# Voltage_Sense.net
KiCad netlist of a schematic drawn in Altium Designer
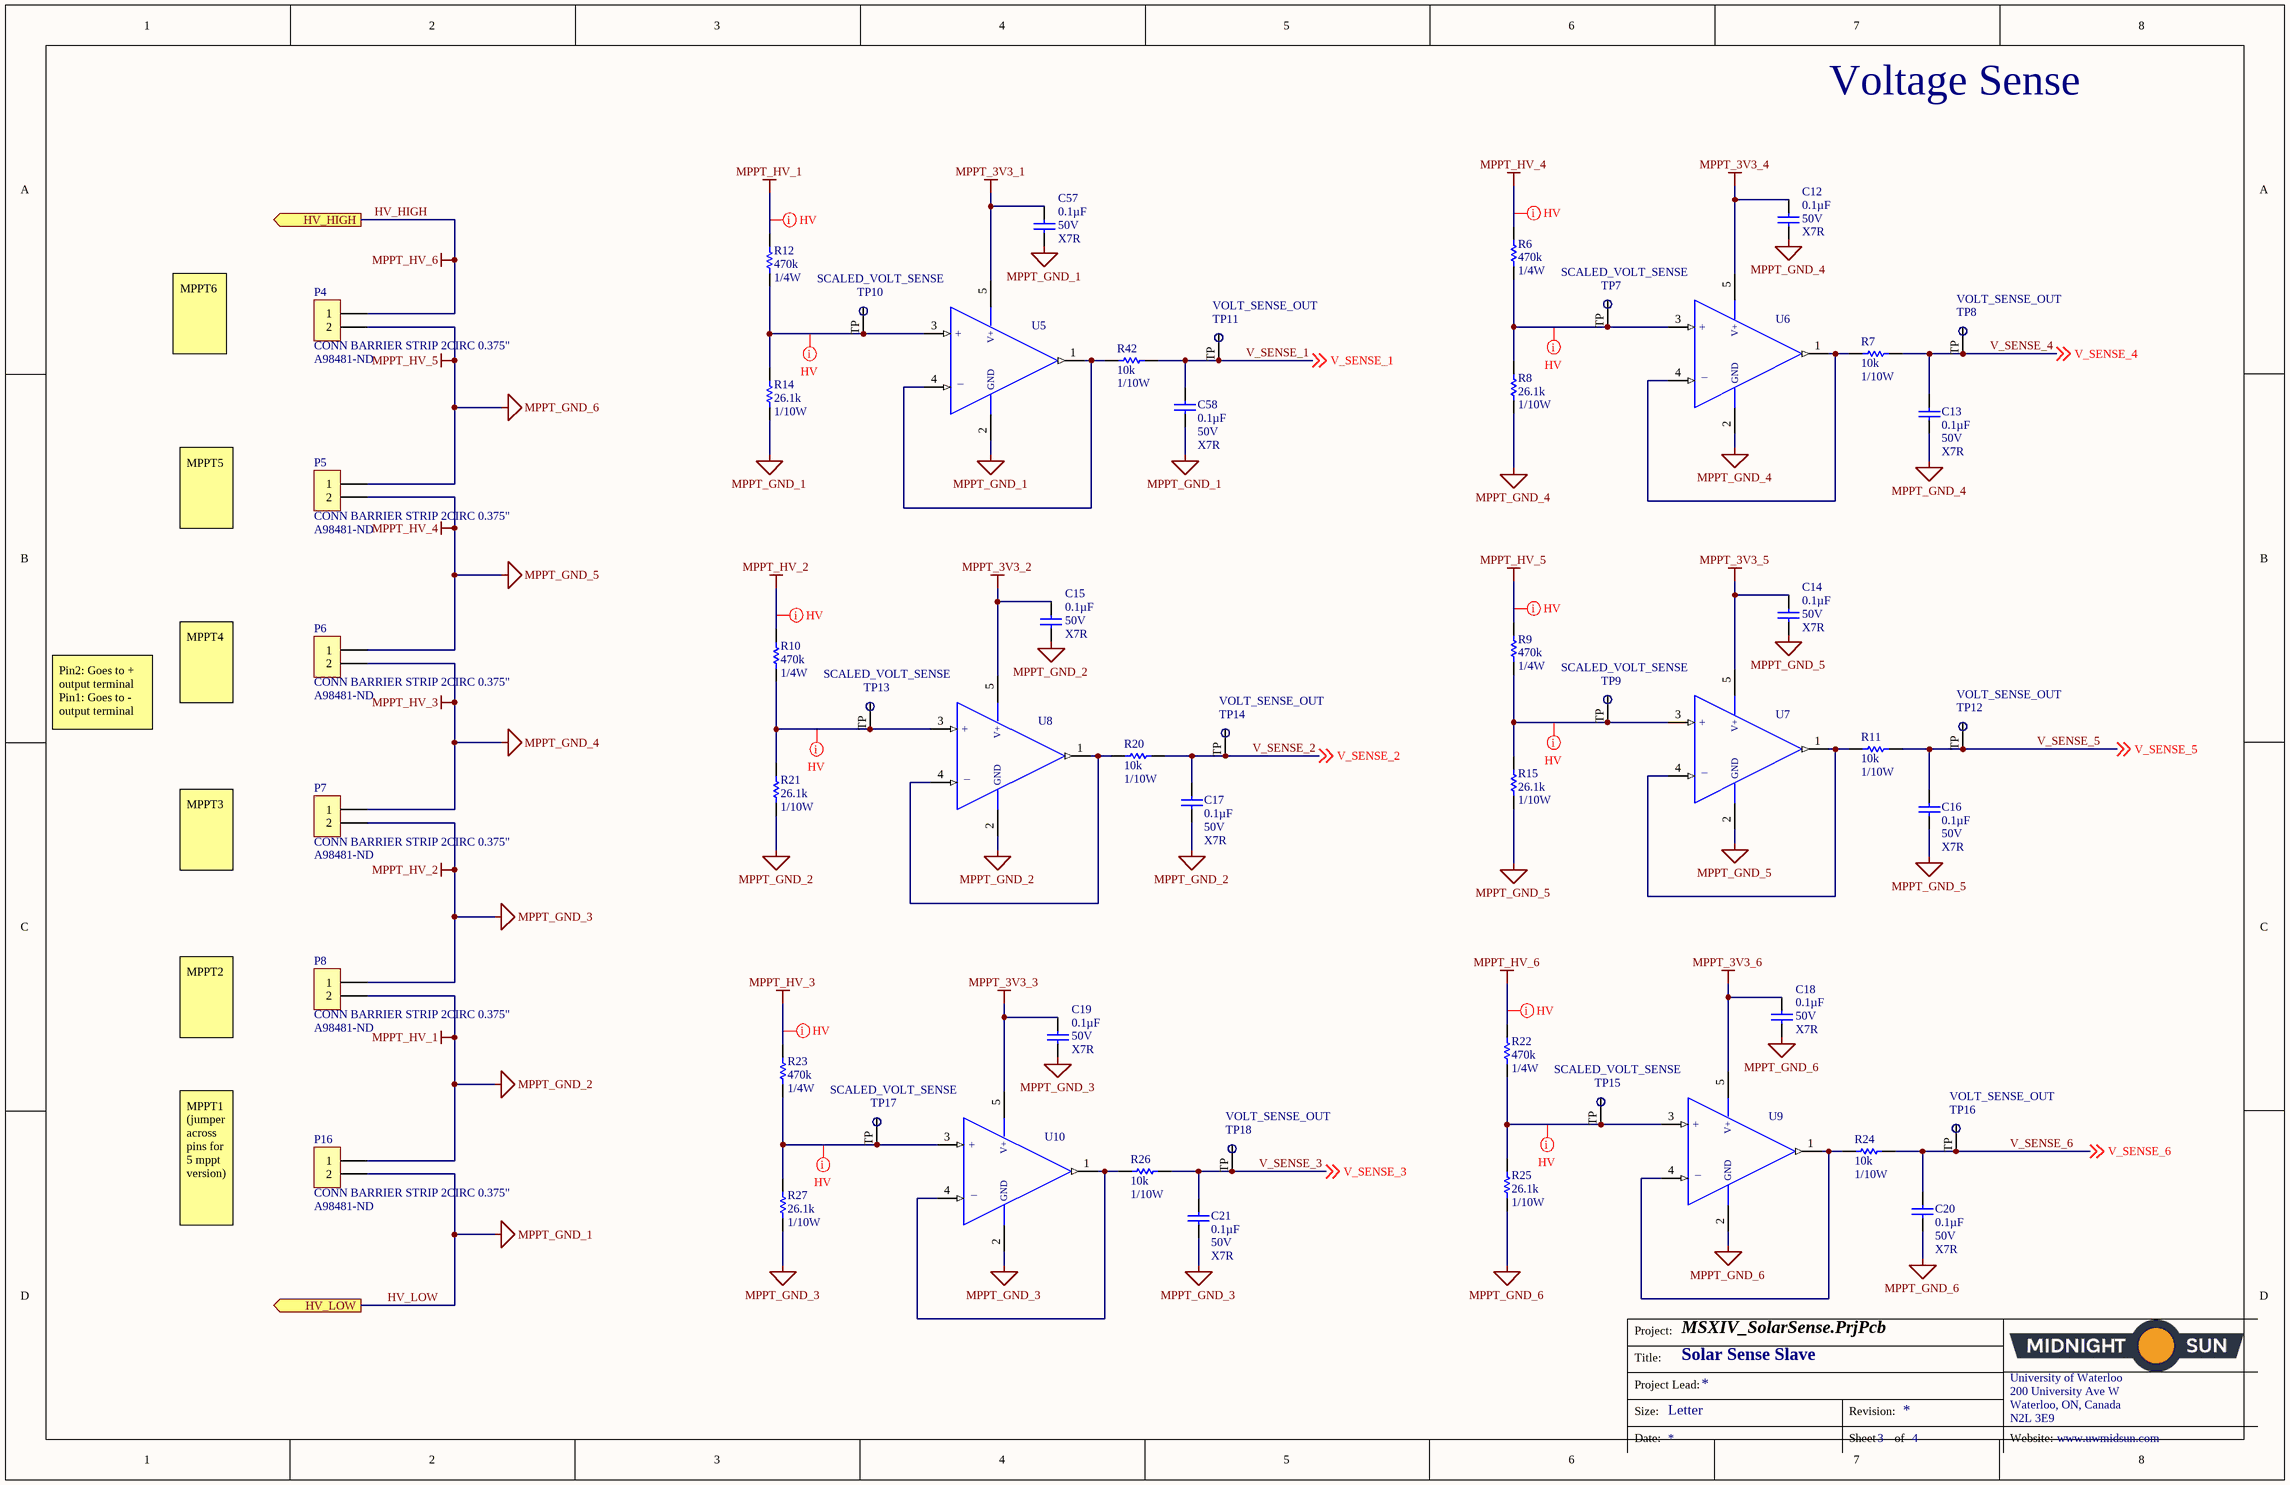
[diagram p0: Voltage_Sense.SchDoc]

(export (version "E")
  (design (tool "Eeschema 10.0.6"))
  (components
    (comp (ref "C12")
      (value "CAP CER 0.1UF 50V 10% X7R 0603")
      (footprint "CAP, 0603")
      (description "0.10µF ±10% 50V Ceramic Capacitor X7R 0603 (1608 Metric)")
      (fields
        (field (name "TOLERANCE") "±10%")
        (field (name "CAPACITANCE") "0.1µF")
        (field (name "VOLTAGE") "50V")
        (field (name "TEMPERATURE COEFFICIENT") "X7R")
      )
      (libsource (lib "Schematic Diagrams") (part "CAP CER 0.1UF 50V 10% X7R 0603"))
    )
    (comp (ref "C13")
      (value "CAP CER 0.1UF 50V 10% X7R 0603")
      (footprint "CAP, 0603")
      (description "0.10µF ±10% 50V Ceramic Capacitor X7R 0603 (1608 Metric)")
      (fields
        (field (name "TOLERANCE") "±10%")
        (field (name "CAPACITANCE") "0.1µF")
        (field (name "VOLTAGE") "50V")
        (field (name "TEMPERATURE COEFFICIENT") "X7R")
      )
      (libsource (lib "Schematic Diagrams") (part "CAP CER 0.1UF 50V 10% X7R 0603"))
    )
    (comp (ref "C14")
      (value "CAP CER 0.1UF 50V 10% X7R 0603")
      (footprint "CAP, 0603")
      (description "0.10µF ±10% 50V Ceramic Capacitor X7R 0603 (1608 Metric)")
      (fields
        (field (name "TOLERANCE") "±10%")
        (field (name "CAPACITANCE") "0.1µF")
        (field (name "VOLTAGE") "50V")
        (field (name "TEMPERATURE COEFFICIENT") "X7R")
      )
      (libsource (lib "Schematic Diagrams") (part "CAP CER 0.1UF 50V 10% X7R 0603"))
    )
    (comp (ref "C15")
      (value "CAP CER 0.1UF 50V 10% X7R 0603")
      (footprint "CAP, 0603")
      (description "0.10µF ±10% 50V Ceramic Capacitor X7R 0603 (1608 Metric)")
      (fields
        (field (name "TOLERANCE") "±10%")
        (field (name "CAPACITANCE") "0.1µF")
        (field (name "VOLTAGE") "50V")
        (field (name "TEMPERATURE COEFFICIENT") "X7R")
      )
      (libsource (lib "Schematic Diagrams") (part "CAP CER 0.1UF 50V 10% X7R 0603"))
    )
    (comp (ref "C16")
      (value "CAP CER 0.1UF 50V 10% X7R 0603")
      (footprint "CAP, 0603")
      (description "0.10µF ±10% 50V Ceramic Capacitor X7R 0603 (1608 Metric)")
      (fields
        (field (name "TOLERANCE") "±10%")
        (field (name "CAPACITANCE") "0.1µF")
        (field (name "VOLTAGE") "50V")
        (field (name "TEMPERATURE COEFFICIENT") "X7R")
      )
      (libsource (lib "Schematic Diagrams") (part "CAP CER 0.1UF 50V 10% X7R 0603"))
    )
    (comp (ref "C17")
      (value "CAP CER 0.1UF 50V 10% X7R 0603")
      (footprint "CAP, 0603")
      (description "0.10µF ±10% 50V Ceramic Capacitor X7R 0603 (1608 Metric)")
      (fields
        (field (name "TOLERANCE") "±10%")
        (field (name "CAPACITANCE") "0.1µF")
        (field (name "VOLTAGE") "50V")
        (field (name "TEMPERATURE COEFFICIENT") "X7R")
      )
      (libsource (lib "Schematic Diagrams") (part "CAP CER 0.1UF 50V 10% X7R 0603"))
    )
    (comp (ref "C18")
      (value "CAP CER 0.1UF 50V 10% X7R 0603")
      (footprint "CAP, 0603")
      (description "0.10µF ±10% 50V Ceramic Capacitor X7R 0603 (1608 Metric)")
      (fields
        (field (name "TOLERANCE") "±10%")
        (field (name "CAPACITANCE") "0.1µF")
        (field (name "VOLTAGE") "50V")
        (field (name "TEMPERATURE COEFFICIENT") "X7R")
      )
      (libsource (lib "Schematic Diagrams") (part "CAP CER 0.1UF 50V 10% X7R 0603"))
    )
    (comp (ref "C19")
      (value "CAP CER 0.1UF 50V 10% X7R 0603")
      (footprint "CAP, 0603")
      (description "0.10µF ±10% 50V Ceramic Capacitor X7R 0603 (1608 Metric)")
      (fields
        (field (name "TOLERANCE") "±10%")
        (field (name "CAPACITANCE") "0.1µF")
        (field (name "VOLTAGE") "50V")
        (field (name "TEMPERATURE COEFFICIENT") "X7R")
      )
      (libsource (lib "Schematic Diagrams") (part "CAP CER 0.1UF 50V 10% X7R 0603"))
    )
    (comp (ref "C20")
      (value "CAP CER 0.1UF 50V 10% X7R 0603")
      (footprint "CAP, 0603")
      (description "0.10µF ±10% 50V Ceramic Capacitor X7R 0603 (1608 Metric)")
      (fields
        (field (name "TOLERANCE") "±10%")
        (field (name "CAPACITANCE") "0.1µF")
        (field (name "VOLTAGE") "50V")
        (field (name "TEMPERATURE COEFFICIENT") "X7R")
      )
      (libsource (lib "Schematic Diagrams") (part "CAP CER 0.1UF 50V 10% X7R 0603"))
    )
    (comp (ref "C21")
      (value "CAP CER 0.1UF 50V 10% X7R 0603")
      (footprint "CAP, 0603")
      (description "0.10µF ±10% 50V Ceramic Capacitor X7R 0603 (1608 Metric)")
      (fields
        (field (name "TOLERANCE") "±10%")
        (field (name "CAPACITANCE") "0.1µF")
        (field (name "VOLTAGE") "50V")
        (field (name "TEMPERATURE COEFFICIENT") "X7R")
      )
      (libsource (lib "Schematic Diagrams") (part "CAP CER 0.1UF 50V 10% X7R 0603"))
    )
    (comp (ref "C57")
      (value "CAP CER 0.1UF 50V 10% X7R 0603")
      (footprint "CAP, 0603")
      (description "0.10µF ±10% 50V Ceramic Capacitor X7R 0603 (1608 Metric)")
      (fields
        (field (name "TOLERANCE") "±10%")
        (field (name "CAPACITANCE") "0.1µF")
        (field (name "VOLTAGE") "50V")
        (field (name "TEMPERATURE COEFFICIENT") "X7R")
      )
      (libsource (lib "Schematic Diagrams") (part "CAP CER 0.1UF 50V 10% X7R 0603"))
    )
    (comp (ref "C58")
      (value "CAP CER 0.1UF 50V 10% X7R 0603")
      (footprint "CAP, 0603")
      (description "0.10µF ±10% 50V Ceramic Capacitor X7R 0603 (1608 Metric)")
      (fields
        (field (name "TOLERANCE") "±10%")
        (field (name "CAPACITANCE") "0.1µF")
        (field (name "VOLTAGE") "50V")
        (field (name "TEMPERATURE COEFFICIENT") "X7R")
      )
      (libsource (lib "Schematic Diagrams") (part "CAP CER 0.1UF 50V 10% X7R 0603"))
    )
    (comp (ref "P4")
      (value "CONN BARRIER STRIP 2CIRC 0.375\"")
      (footprint "TE_3-1437652-9")
      (description "Barrier Terminal Blocks 2P TRI-BARRIER .375")
      (fields
        (field (name "MANUFACTURER") "TE Connectivity")
        (field (name "MANUFACTURER PART NUMBER") "6PCV-02-006")
        (field (name "SUPPLIER PART NUMBER 1") "A98481-ND")
      )
      (libsource (lib "Schematic Diagrams") (part "CONN BARRIER STRIP 2CIRC 0.375{dblquote}"))
    )
    (comp (ref "P5")
      (value "CONN BARRIER STRIP 2CIRC 0.375\"")
      (footprint "TE_3-1437652-9")
      (description "Barrier Terminal Blocks 2P TRI-BARRIER .375")
      (fields
        (field (name "MANUFACTURER") "TE Connectivity")
        (field (name "MANUFACTURER PART NUMBER") "6PCV-02-006")
        (field (name "SUPPLIER PART NUMBER 1") "A98481-ND")
      )
      (libsource (lib "Schematic Diagrams") (part "CONN BARRIER STRIP 2CIRC 0.375{dblquote}"))
    )
    (comp (ref "P6")
      (value "CONN BARRIER STRIP 2CIRC 0.375\"")
      (footprint "TE_3-1437652-9")
      (description "Barrier Terminal Blocks 2P TRI-BARRIER .375")
      (fields
        (field (name "MANUFACTURER") "TE Connectivity")
        (field (name "MANUFACTURER PART NUMBER") "6PCV-02-006")
        (field (name "SUPPLIER PART NUMBER 1") "A98481-ND")
      )
      (libsource (lib "Schematic Diagrams") (part "CONN BARRIER STRIP 2CIRC 0.375{dblquote}"))
    )
    (comp (ref "P7")
      (value "CONN BARRIER STRIP 2CIRC 0.375\"")
      (footprint "TE_3-1437652-9")
      (description "Barrier Terminal Blocks 2P TRI-BARRIER .375")
      (fields
        (field (name "MANUFACTURER") "TE Connectivity")
        (field (name "MANUFACTURER PART NUMBER") "6PCV-02-006")
        (field (name "SUPPLIER PART NUMBER 1") "A98481-ND")
      )
      (libsource (lib "Schematic Diagrams") (part "CONN BARRIER STRIP 2CIRC 0.375{dblquote}"))
    )
    (comp (ref "P8")
      (value "CONN BARRIER STRIP 2CIRC 0.375\"")
      (footprint "TE_3-1437652-9")
      (description "Barrier Terminal Blocks 2P TRI-BARRIER .375")
      (fields
        (field (name "MANUFACTURER") "TE Connectivity")
        (field (name "MANUFACTURER PART NUMBER") "6PCV-02-006")
        (field (name "SUPPLIER PART NUMBER 1") "A98481-ND")
      )
      (libsource (lib "Schematic Diagrams") (part "CONN BARRIER STRIP 2CIRC 0.375{dblquote}"))
    )
    (comp (ref "P16")
      (value "CONN BARRIER STRIP 2CIRC 0.375\"")
      (footprint "TE_3-1437652-9")
      (description "Barrier Terminal Blocks 2P TRI-BARRIER .375")
      (fields
        (field (name "MANUFACTURER") "TE Connectivity")
        (field (name "MANUFACTURER PART NUMBER") "6PCV-02-006")
        (field (name "SUPPLIER PART NUMBER 1") "A98481-ND")
      )
      (libsource (lib "Schematic Diagrams") (part "CONN BARRIER STRIP 2CIRC 0.375{dblquote}"))
    )
    (comp (ref "R6")
      (value "RES 470K OHM 1% 1/4W 0603")
      (footprint "RES, 0603")
      (description "RES SMD 470K OHM 1% 1/4W 0603")
      (fields
        (field (name "TOLERANCE") "±1%")
        (field (name "RESISTANCE") "470k")
        (field (name "POWER") "1/4W")
      )
      (libsource (lib "Schematic Diagrams") (part "RES 470K OHM 1% 1/4W 0603"))
    )
    (comp (ref "R7")
      (value "RES 10K OHM 1% 1/10W 0603")
      (footprint "RES, 0603")
      (description "RES SMD 10K OHM 1% 1/10W 0603")
      (fields
        (field (name "TOLERANCE") "±1%")
        (field (name "RESISTANCE") "10k")
        (field (name "POWER") "1/10W")
      )
      (libsource (lib "Schematic Diagrams") (part "RES 10K OHM 1% 1/10W 0603"))
    )
    (comp (ref "R8")
      (value "RES 26.1K OHM 1% 1/10W 0603")
      (footprint "RES, 0603")
      (description "RES SMD 26.1K OHM 1% 1/10W 0603")
      (fields
        (field (name "TOLERANCE") "±1%")
        (field (name "RESISTANCE") "26.1k")
        (field (name "POWER") "1/10W")
      )
      (libsource (lib "Schematic Diagrams") (part "RES 26.1K OHM 1% 1/10W 0603"))
    )
    (comp (ref "R9")
      (value "RES 470K OHM 1% 1/4W 0603")
      (footprint "RES, 0603")
      (description "RES SMD 470K OHM 1% 1/4W 0603")
      (fields
        (field (name "TOLERANCE") "±1%")
        (field (name "RESISTANCE") "470k")
        (field (name "POWER") "1/4W")
      )
      (libsource (lib "Schematic Diagrams") (part "RES 470K OHM 1% 1/4W 0603"))
    )
    (comp (ref "R10")
      (value "RES 470K OHM 1% 1/4W 0603")
      (footprint "RES, 0603")
      (description "RES SMD 470K OHM 1% 1/4W 0603")
      (fields
        (field (name "TOLERANCE") "±1%")
        (field (name "RESISTANCE") "470k")
        (field (name "POWER") "1/4W")
      )
      (libsource (lib "Schematic Diagrams") (part "RES 470K OHM 1% 1/4W 0603"))
    )
    (comp (ref "R11")
      (value "RES 10K OHM 1% 1/10W 0603")
      (footprint "RES, 0603")
      (description "RES SMD 10K OHM 1% 1/10W 0603")
      (fields
        (field (name "TOLERANCE") "±1%")
        (field (name "RESISTANCE") "10k")
        (field (name "POWER") "1/10W")
      )
      (libsource (lib "Schematic Diagrams") (part "RES 10K OHM 1% 1/10W 0603"))
    )
    (comp (ref "R12")
      (value "RES 470K OHM 1% 1/4W 0603")
      (footprint "RES, 0603")
      (description "RES SMD 470K OHM 1% 1/4W 0603")
      (fields
        (field (name "TOLERANCE") "±1%")
        (field (name "RESISTANCE") "470k")
        (field (name "POWER") "1/4W")
      )
      (libsource (lib "Schematic Diagrams") (part "RES 470K OHM 1% 1/4W 0603"))
    )
    (comp (ref "R14")
      (value "RES 26.1K OHM 1% 1/10W 0603")
      (footprint "RES, 0603")
      (description "RES SMD 26.1K OHM 1% 1/10W 0603")
      (fields
        (field (name "TOLERANCE") "±1%")
        (field (name "RESISTANCE") "26.1k")
        (field (name "POWER") "1/10W")
      )
      (libsource (lib "Schematic Diagrams") (part "RES 26.1K OHM 1% 1/10W 0603"))
    )
    (comp (ref "R15")
      (value "RES 26.1K OHM 1% 1/10W 0603")
      (footprint "RES, 0603")
      (description "RES SMD 26.1K OHM 1% 1/10W 0603")
      (fields
        (field (name "TOLERANCE") "±1%")
        (field (name "RESISTANCE") "26.1k")
        (field (name "POWER") "1/10W")
      )
      (libsource (lib "Schematic Diagrams") (part "RES 26.1K OHM 1% 1/10W 0603"))
    )
    (comp (ref "R20")
      (value "RES 10K OHM 1% 1/10W 0603")
      (footprint "RES, 0603")
      (description "RES SMD 10K OHM 1% 1/10W 0603")
      (fields
        (field (name "TOLERANCE") "±1%")
        (field (name "RESISTANCE") "10k")
        (field (name "POWER") "1/10W")
      )
      (libsource (lib "Schematic Diagrams") (part "RES 10K OHM 1% 1/10W 0603"))
    )
    (comp (ref "R21")
      (value "RES 26.1K OHM 1% 1/10W 0603")
      (footprint "RES, 0603")
      (description "RES SMD 26.1K OHM 1% 1/10W 0603")
      (fields
        (field (name "TOLERANCE") "±1%")
        (field (name "RESISTANCE") "26.1k")
        (field (name "POWER") "1/10W")
      )
      (libsource (lib "Schematic Diagrams") (part "RES 26.1K OHM 1% 1/10W 0603"))
    )
    (comp (ref "R22")
      (value "RES 470K OHM 1% 1/4W 0603")
      (footprint "RES, 0603")
      (description "RES SMD 470K OHM 1% 1/4W 0603")
      (fields
        (field (name "TOLERANCE") "±1%")
        (field (name "RESISTANCE") "470k")
        (field (name "POWER") "1/4W")
      )
      (libsource (lib "Schematic Diagrams") (part "RES 470K OHM 1% 1/4W 0603"))
    )
    (comp (ref "R23")
      (value "RES 470K OHM 1% 1/4W 0603")
      (footprint "RES, 0603")
      (description "RES SMD 470K OHM 1% 1/4W 0603")
      (fields
        (field (name "TOLERANCE") "±1%")
        (field (name "RESISTANCE") "470k")
        (field (name "POWER") "1/4W")
      )
      (libsource (lib "Schematic Diagrams") (part "RES 470K OHM 1% 1/4W 0603"))
    )
    (comp (ref "R24")
      (value "RES 10K OHM 1% 1/10W 0603")
      (footprint "RES, 0603")
      (description "RES SMD 10K OHM 1% 1/10W 0603")
      (fields
        (field (name "TOLERANCE") "±1%")
        (field (name "RESISTANCE") "10k")
        (field (name "POWER") "1/10W")
      )
      (libsource (lib "Schematic Diagrams") (part "RES 10K OHM 1% 1/10W 0603"))
    )
    (comp (ref "R25")
      (value "RES 26.1K OHM 1% 1/10W 0603")
      (footprint "RES, 0603")
      (description "RES SMD 26.1K OHM 1% 1/10W 0603")
      (fields
        (field (name "TOLERANCE") "±1%")
        (field (name "RESISTANCE") "26.1k")
        (field (name "POWER") "1/10W")
      )
      (libsource (lib "Schematic Diagrams") (part "RES 26.1K OHM 1% 1/10W 0603"))
    )
    (comp (ref "R26")
      (value "RES 10K OHM 1% 1/10W 0603")
      (footprint "RES, 0603")
      (description "RES SMD 10K OHM 1% 1/10W 0603")
      (fields
        (field (name "TOLERANCE") "±1%")
        (field (name "RESISTANCE") "10k")
        (field (name "POWER") "1/10W")
      )
      (libsource (lib "Schematic Diagrams") (part "RES 10K OHM 1% 1/10W 0603"))
    )
    (comp (ref "R27")
      (value "RES 26.1K OHM 1% 1/10W 0603")
      (footprint "RES, 0603")
      (description "RES SMD 26.1K OHM 1% 1/10W 0603")
      (fields
        (field (name "TOLERANCE") "±1%")
        (field (name "RESISTANCE") "26.1k")
        (field (name "POWER") "1/10W")
      )
      (libsource (lib "Schematic Diagrams") (part "RES 26.1K OHM 1% 1/10W 0603"))
    )
    (comp (ref "R42")
      (value "RES 10K OHM 1% 1/10W 0603")
      (footprint "RES, 0603")
      (description "RES SMD 10K OHM 1% 1/10W 0603")
      (fields
        (field (name "TOLERANCE") "±1%")
        (field (name "RESISTANCE") "10k")
        (field (name "POWER") "1/10W")
      )
      (libsource (lib "Schematic Diagrams") (part "RES 10K OHM 1% 1/10W 0603"))
    )
    (comp (ref "TP7")
      (value "SCALED_VOLT_SENSE")
      (footprint "Test Point")
      (libsource (lib "Schematic Diagrams") (part "Test Point"))
    )
    (comp (ref "TP8")
      (value "VOLT_SENSE_OUT")
      (footprint "Test Point")
      (libsource (lib "Schematic Diagrams") (part "Test Point"))
    )
    (comp (ref "TP9")
      (value "SCALED_VOLT_SENSE")
      (footprint "Test Point")
      (libsource (lib "Schematic Diagrams") (part "Test Point"))
    )
    (comp (ref "TP10")
      (value "SCALED_VOLT_SENSE")
      (footprint "Test Point")
      (libsource (lib "Schematic Diagrams") (part "Test Point"))
    )
    (comp (ref "TP11")
      (value "VOLT_SENSE_OUT")
      (footprint "Test Point")
      (libsource (lib "Schematic Diagrams") (part "Test Point"))
    )
    (comp (ref "TP12")
      (value "VOLT_SENSE_OUT")
      (footprint "Test Point")
      (libsource (lib "Schematic Diagrams") (part "Test Point"))
    )
    (comp (ref "TP13")
      (value "SCALED_VOLT_SENSE")
      (footprint "Test Point")
      (libsource (lib "Schematic Diagrams") (part "Test Point"))
    )
    (comp (ref "TP14")
      (value "VOLT_SENSE_OUT")
      (footprint "Test Point")
      (libsource (lib "Schematic Diagrams") (part "Test Point"))
    )
    (comp (ref "TP15")
      (value "SCALED_VOLT_SENSE")
      (footprint "Test Point")
      (libsource (lib "Schematic Diagrams") (part "Test Point"))
    )
    (comp (ref "TP16")
      (value "VOLT_SENSE_OUT")
      (footprint "Test Point")
      (libsource (lib "Schematic Diagrams") (part "Test Point"))
    )
    (comp (ref "TP17")
      (value "SCALED_VOLT_SENSE")
      (footprint "Test Point")
      (libsource (lib "Schematic Diagrams") (part "Test Point"))
    )
    (comp (ref "TP18")
      (value "VOLT_SENSE_OUT")
      (footprint "Test Point")
      (libsource (lib "Schematic Diagrams") (part "Test Point"))
    )
    (comp (ref "U5")
      (value "IC OP AMP GEN PURPOSE RR 10MHZ SOT-23-5")
      (footprint "IC OP AMP GP RR 10MHZ SOT-23-5")
      (description "General Purpose Amplifier 1 Circuit Rail-to-Rail SOT-23-5")
      (libsource (lib "Schematic Diagrams") (part "IC OP AMP GEN PURPOSE RR 10MHZ SOT-23-5"))
    )
    (comp (ref "U6")
      (value "IC OP AMP GEN PURPOSE RR 10MHZ SOT-23-5")
      (footprint "IC OP AMP GP RR 10MHZ SOT-23-5")
      (description "General Purpose Amplifier 1 Circuit Rail-to-Rail SOT-23-5")
      (libsource (lib "Schematic Diagrams") (part "IC OP AMP GEN PURPOSE RR 10MHZ SOT-23-5"))
    )
    (comp (ref "U7")
      (value "IC OP AMP GEN PURPOSE RR 10MHZ SOT-23-5")
      (footprint "IC OP AMP GP RR 10MHZ SOT-23-5")
      (description "General Purpose Amplifier 1 Circuit Rail-to-Rail SOT-23-5")
      (libsource (lib "Schematic Diagrams") (part "IC OP AMP GEN PURPOSE RR 10MHZ SOT-23-5"))
    )
    (comp (ref "U8")
      (value "IC OP AMP GEN PURPOSE RR 10MHZ SOT-23-5")
      (footprint "IC OP AMP GP RR 10MHZ SOT-23-5")
      (description "General Purpose Amplifier 1 Circuit Rail-to-Rail SOT-23-5")
      (libsource (lib "Schematic Diagrams") (part "IC OP AMP GEN PURPOSE RR 10MHZ SOT-23-5"))
    )
    (comp (ref "U9")
      (value "IC OP AMP GEN PURPOSE RR 10MHZ SOT-23-5")
      (footprint "IC OP AMP GP RR 10MHZ SOT-23-5")
      (description "General Purpose Amplifier 1 Circuit Rail-to-Rail SOT-23-5")
      (libsource (lib "Schematic Diagrams") (part "IC OP AMP GEN PURPOSE RR 10MHZ SOT-23-5"))
    )
    (comp (ref "U10")
      (value "IC OP AMP GEN PURPOSE RR 10MHZ SOT-23-5")
      (footprint "IC OP AMP GP RR 10MHZ SOT-23-5")
      (description "General Purpose Amplifier 1 Circuit Rail-to-Rail SOT-23-5")
      (libsource (lib "Schematic Diagrams") (part "IC OP AMP GEN PURPOSE RR 10MHZ SOT-23-5"))
    )
  )
  (nets
    (net (code "1") (name "MPPT_3V3_1") (class "Default")
      (node (ref "C57") (pin "1") (pinfunction "1_1") (pintype "passive"))
      (node (ref "U5") (pin "5") (pinfunction "VDD_5") (pintype "power_in"))
    )
    (net (code "2") (name "MPPT_3V3_2") (class "Default")
      (node (ref "C15") (pin "1") (pinfunction "1_1") (pintype "passive"))
      (node (ref "U8") (pin "5") (pinfunction "VDD_5") (pintype "power_in"))
    )
    (net (code "3") (name "MPPT_3V3_3") (class "Default")
      (node (ref "C19") (pin "1") (pinfunction "1_1") (pintype "passive"))
      (node (ref "U10") (pin "5") (pinfunction "VDD_5") (pintype "power_in"))
    )
    (net (code "4") (name "MPPT_3V3_4") (class "Default")
      (node (ref "C12") (pin "1") (pinfunction "1_1") (pintype "passive"))
      (node (ref "U6") (pin "5") (pinfunction "VDD_5") (pintype "power_in"))
    )
    (net (code "5") (name "MPPT_3V3_5") (class "Default")
      (node (ref "C14") (pin "1") (pinfunction "1_1") (pintype "passive"))
      (node (ref "U7") (pin "5") (pinfunction "VDD_5") (pintype "power_in"))
    )
    (net (code "6") (name "MPPT_3V3_6") (class "Default")
      (node (ref "C18") (pin "1") (pinfunction "1_1") (pintype "passive"))
      (node (ref "U9") (pin "5") (pinfunction "VDD_5") (pintype "power_in"))
    )
    (net (code "7") (name "MPPT_GND_1") (class "Default")
      (node (ref "C57") (pin "2") (pinfunction "2_2") (pintype "passive"))
      (node (ref "C58") (pin "2") (pinfunction "2_2") (pintype "passive"))
      (node (ref "P16") (pin "2") (pinfunction "2_2") (pintype "passive"))
      (node (ref "R14") (pin "2") (pinfunction "2_2") (pintype "passive"))
      (node (ref "U5") (pin "2") (pinfunction "VSS_2") (pintype "power_in"))
    )
    (net (code "8") (name "MPPT_GND_2") (class "Default")
      (node (ref "C15") (pin "2") (pinfunction "2_2") (pintype "passive"))
      (node (ref "C17") (pin "2") (pinfunction "2_2") (pintype "passive"))
      (node (ref "P16") (pin "1") (pinfunction "1_1") (pintype "passive"))
      (node (ref "P8") (pin "2") (pinfunction "2_2") (pintype "passive"))
      (node (ref "R12") (pin "1") (pinfunction "1_1") (pintype "passive"))
      (node (ref "R21") (pin "2") (pinfunction "2_2") (pintype "passive"))
      (node (ref "U8") (pin "2") (pinfunction "VSS_2") (pintype "power_in"))
    )
    (net (code "9") (name "MPPT_GND_3") (class "Default")
      (node (ref "C19") (pin "2") (pinfunction "2_2") (pintype "passive"))
      (node (ref "C21") (pin "2") (pinfunction "2_2") (pintype "passive"))
      (node (ref "P7") (pin "2") (pinfunction "2_2") (pintype "passive"))
      (node (ref "P8") (pin "1") (pinfunction "1_1") (pintype "passive"))
      (node (ref "R10") (pin "1") (pinfunction "1_1") (pintype "passive"))
      (node (ref "R27") (pin "2") (pinfunction "2_2") (pintype "passive"))
      (node (ref "U10") (pin "2") (pinfunction "VSS_2") (pintype "power_in"))
    )
    (net (code "10") (name "MPPT_GND_4") (class "Default")
      (node (ref "C12") (pin "2") (pinfunction "2_2") (pintype "passive"))
      (node (ref "C13") (pin "2") (pinfunction "2_2") (pintype "passive"))
      (node (ref "P6") (pin "2") (pinfunction "2_2") (pintype "passive"))
      (node (ref "P7") (pin "1") (pinfunction "1_1") (pintype "passive"))
      (node (ref "R23") (pin "1") (pinfunction "1_1") (pintype "passive"))
      (node (ref "R8") (pin "2") (pinfunction "2_2") (pintype "passive"))
      (node (ref "U6") (pin "2") (pinfunction "VSS_2") (pintype "power_in"))
    )
    (net (code "11") (name "MPPT_GND_5") (class "Default")
      (node (ref "C14") (pin "2") (pinfunction "2_2") (pintype "passive"))
      (node (ref "C16") (pin "2") (pinfunction "2_2") (pintype "passive"))
      (node (ref "P5") (pin "2") (pinfunction "2_2") (pintype "passive"))
      (node (ref "P6") (pin "1") (pinfunction "1_1") (pintype "passive"))
      (node (ref "R15") (pin "2") (pinfunction "2_2") (pintype "passive"))
      (node (ref "R6") (pin "1") (pinfunction "1_1") (pintype "passive"))
      (node (ref "U7") (pin "2") (pinfunction "VSS_2") (pintype "power_in"))
    )
    (net (code "12") (name "MPPT_GND_6") (class "Default")
      (node (ref "C18") (pin "2") (pinfunction "2_2") (pintype "passive"))
      (node (ref "C20") (pin "2") (pinfunction "2_2") (pintype "passive"))
      (node (ref "P4") (pin "2") (pinfunction "2_2") (pintype "passive"))
      (node (ref "P5") (pin "1") (pinfunction "1_1") (pintype "passive"))
      (node (ref "R25") (pin "2") (pinfunction "2_2") (pintype "passive"))
      (node (ref "R9") (pin "1") (pinfunction "1_1") (pintype "passive"))
      (node (ref "U9") (pin "2") (pinfunction "VSS_2") (pintype "power_in"))
    )
    (net (code "13") (name "MPPT_HV_6") (class "Default")
      (node (ref "P4") (pin "1") (pinfunction "1_1") (pintype "passive"))
      (node (ref "R22") (pin "1") (pinfunction "1_1") (pintype "passive"))
    )
    (net (code "14") (name "Net-(TP7-1)") (class "Default")
      (node (ref "R6") (pin "2") (pinfunction "2_2") (pintype "passive"))
      (node (ref "R8") (pin "1") (pinfunction "1_1") (pintype "passive"))
      (node (ref "TP7") (pin "TP") (pinfunction "1_TP") (pintype "passive"))
      (node (ref "U6") (pin "3") (pinfunction "+IN_3") (pintype "input"))
    )
    (net (code "15") (name "Net-(TP9-1)") (class "Default")
      (node (ref "R15") (pin "1") (pinfunction "1_1") (pintype "passive"))
      (node (ref "R9") (pin "2") (pinfunction "2_2") (pintype "passive"))
      (node (ref "TP9") (pin "TP") (pinfunction "1_TP") (pintype "passive"))
      (node (ref "U7") (pin "3") (pinfunction "+IN_3") (pintype "input"))
    )
    (net (code "16") (name "Net-(TP10-1)") (class "Default")
      (node (ref "R12") (pin "2") (pinfunction "2_2") (pintype "passive"))
      (node (ref "R14") (pin "1") (pinfunction "1_1") (pintype "passive"))
      (node (ref "TP10") (pin "TP") (pinfunction "1_TP") (pintype "passive"))
      (node (ref "U5") (pin "3") (pinfunction "+IN_3") (pintype "input"))
    )
    (net (code "17") (name "Net-(TP13-1)") (class "Default")
      (node (ref "R10") (pin "2") (pinfunction "2_2") (pintype "passive"))
      (node (ref "R21") (pin "1") (pinfunction "1_1") (pintype "passive"))
      (node (ref "TP13") (pin "TP") (pinfunction "1_TP") (pintype "passive"))
      (node (ref "U8") (pin "3") (pinfunction "+IN_3") (pintype "input"))
    )
    (net (code "18") (name "Net-(TP15-1)") (class "Default")
      (node (ref "R22") (pin "2") (pinfunction "2_2") (pintype "passive"))
      (node (ref "R25") (pin "1") (pinfunction "1_1") (pintype "passive"))
      (node (ref "TP15") (pin "TP") (pinfunction "1_TP") (pintype "passive"))
      (node (ref "U9") (pin "3") (pinfunction "+IN_3") (pintype "input"))
    )
    (net (code "19") (name "Net-(TP17-1)") (class "Default")
      (node (ref "R23") (pin "2") (pinfunction "2_2") (pintype "passive"))
      (node (ref "R27") (pin "1") (pinfunction "1_1") (pintype "passive"))
      (node (ref "TP17") (pin "TP") (pinfunction "1_TP") (pintype "passive"))
      (node (ref "U10") (pin "3") (pinfunction "+IN_3") (pintype "input"))
    )
    (net (code "20") (name "Net-(U5--IN)") (class "Default")
      (node (ref "R42") (pin "1") (pinfunction "1_1") (pintype "passive"))
      (node (ref "U5") (pin "1") (pinfunction "OUTPUT_1") (pintype "output"))
      (node (ref "U5") (pin "4") (pinfunction "-IN_4") (pintype "input"))
    )
    (net (code "21") (name "Net-(U6--IN)") (class "Default")
      (node (ref "R7") (pin "1") (pinfunction "1_1") (pintype "passive"))
      (node (ref "U6") (pin "1") (pinfunction "OUTPUT_1") (pintype "output"))
      (node (ref "U6") (pin "4") (pinfunction "-IN_4") (pintype "input"))
    )
    (net (code "22") (name "Net-(U7--IN)") (class "Default")
      (node (ref "R11") (pin "1") (pinfunction "1_1") (pintype "passive"))
      (node (ref "U7") (pin "1") (pinfunction "OUTPUT_1") (pintype "output"))
      (node (ref "U7") (pin "4") (pinfunction "-IN_4") (pintype "input"))
    )
    (net (code "23") (name "Net-(U8--IN)") (class "Default")
      (node (ref "R20") (pin "1") (pinfunction "1_1") (pintype "passive"))
      (node (ref "U8") (pin "1") (pinfunction "OUTPUT_1") (pintype "output"))
      (node (ref "U8") (pin "4") (pinfunction "-IN_4") (pintype "input"))
    )
    (net (code "24") (name "Net-(U9--IN)") (class "Default")
      (node (ref "R24") (pin "1") (pinfunction "1_1") (pintype "passive"))
      (node (ref "U9") (pin "1") (pinfunction "OUTPUT_1") (pintype "output"))
      (node (ref "U9") (pin "4") (pinfunction "-IN_4") (pintype "input"))
    )
    (net (code "25") (name "Net-(U10--IN)") (class "Default")
      (node (ref "R26") (pin "1") (pinfunction "1_1") (pintype "passive"))
      (node (ref "U10") (pin "1") (pinfunction "OUTPUT_1") (pintype "output"))
      (node (ref "U10") (pin "4") (pinfunction "-IN_4") (pintype "input"))
    )
    (net (code "26") (name "V_SENSE_1") (class "Default")
      (node (ref "C58") (pin "1") (pinfunction "1_1") (pintype "passive"))
      (node (ref "R42") (pin "2") (pinfunction "2_2") (pintype "passive"))
      (node (ref "TP11") (pin "TP") (pinfunction "1_TP") (pintype "passive"))
    )
    (net (code "27") (name "V_SENSE_2") (class "Default")
      (node (ref "C17") (pin "1") (pinfunction "1_1") (pintype "passive"))
      (node (ref "R20") (pin "2") (pinfunction "2_2") (pintype "passive"))
      (node (ref "TP14") (pin "TP") (pinfunction "1_TP") (pintype "passive"))
    )
    (net (code "28") (name "V_SENSE_3") (class "Default")
      (node (ref "C21") (pin "1") (pinfunction "1_1") (pintype "passive"))
      (node (ref "R26") (pin "2") (pinfunction "2_2") (pintype "passive"))
      (node (ref "TP18") (pin "TP") (pinfunction "1_TP") (pintype "passive"))
    )
    (net (code "29") (name "V_SENSE_4") (class "Default")
      (node (ref "C13") (pin "1") (pinfunction "1_1") (pintype "passive"))
      (node (ref "R7") (pin "2") (pinfunction "2_2") (pintype "passive"))
      (node (ref "TP8") (pin "TP") (pinfunction "1_TP") (pintype "passive"))
    )
    (net (code "30") (name "V_SENSE_5") (class "Default")
      (node (ref "C16") (pin "1") (pinfunction "1_1") (pintype "passive"))
      (node (ref "R11") (pin "2") (pinfunction "2_2") (pintype "passive"))
      (node (ref "TP12") (pin "TP") (pinfunction "1_TP") (pintype "passive"))
    )
    (net (code "31") (name "V_SENSE_6") (class "Default")
      (node (ref "C20") (pin "1") (pinfunction "1_1") (pintype "passive"))
      (node (ref "R24") (pin "2") (pinfunction "2_2") (pintype "passive"))
      (node (ref "TP16") (pin "TP") (pinfunction "1_TP") (pintype "passive"))
    )
  )
)
